# Sheet1.net
KiCad netlist of a schematic drawn in Altium Designer
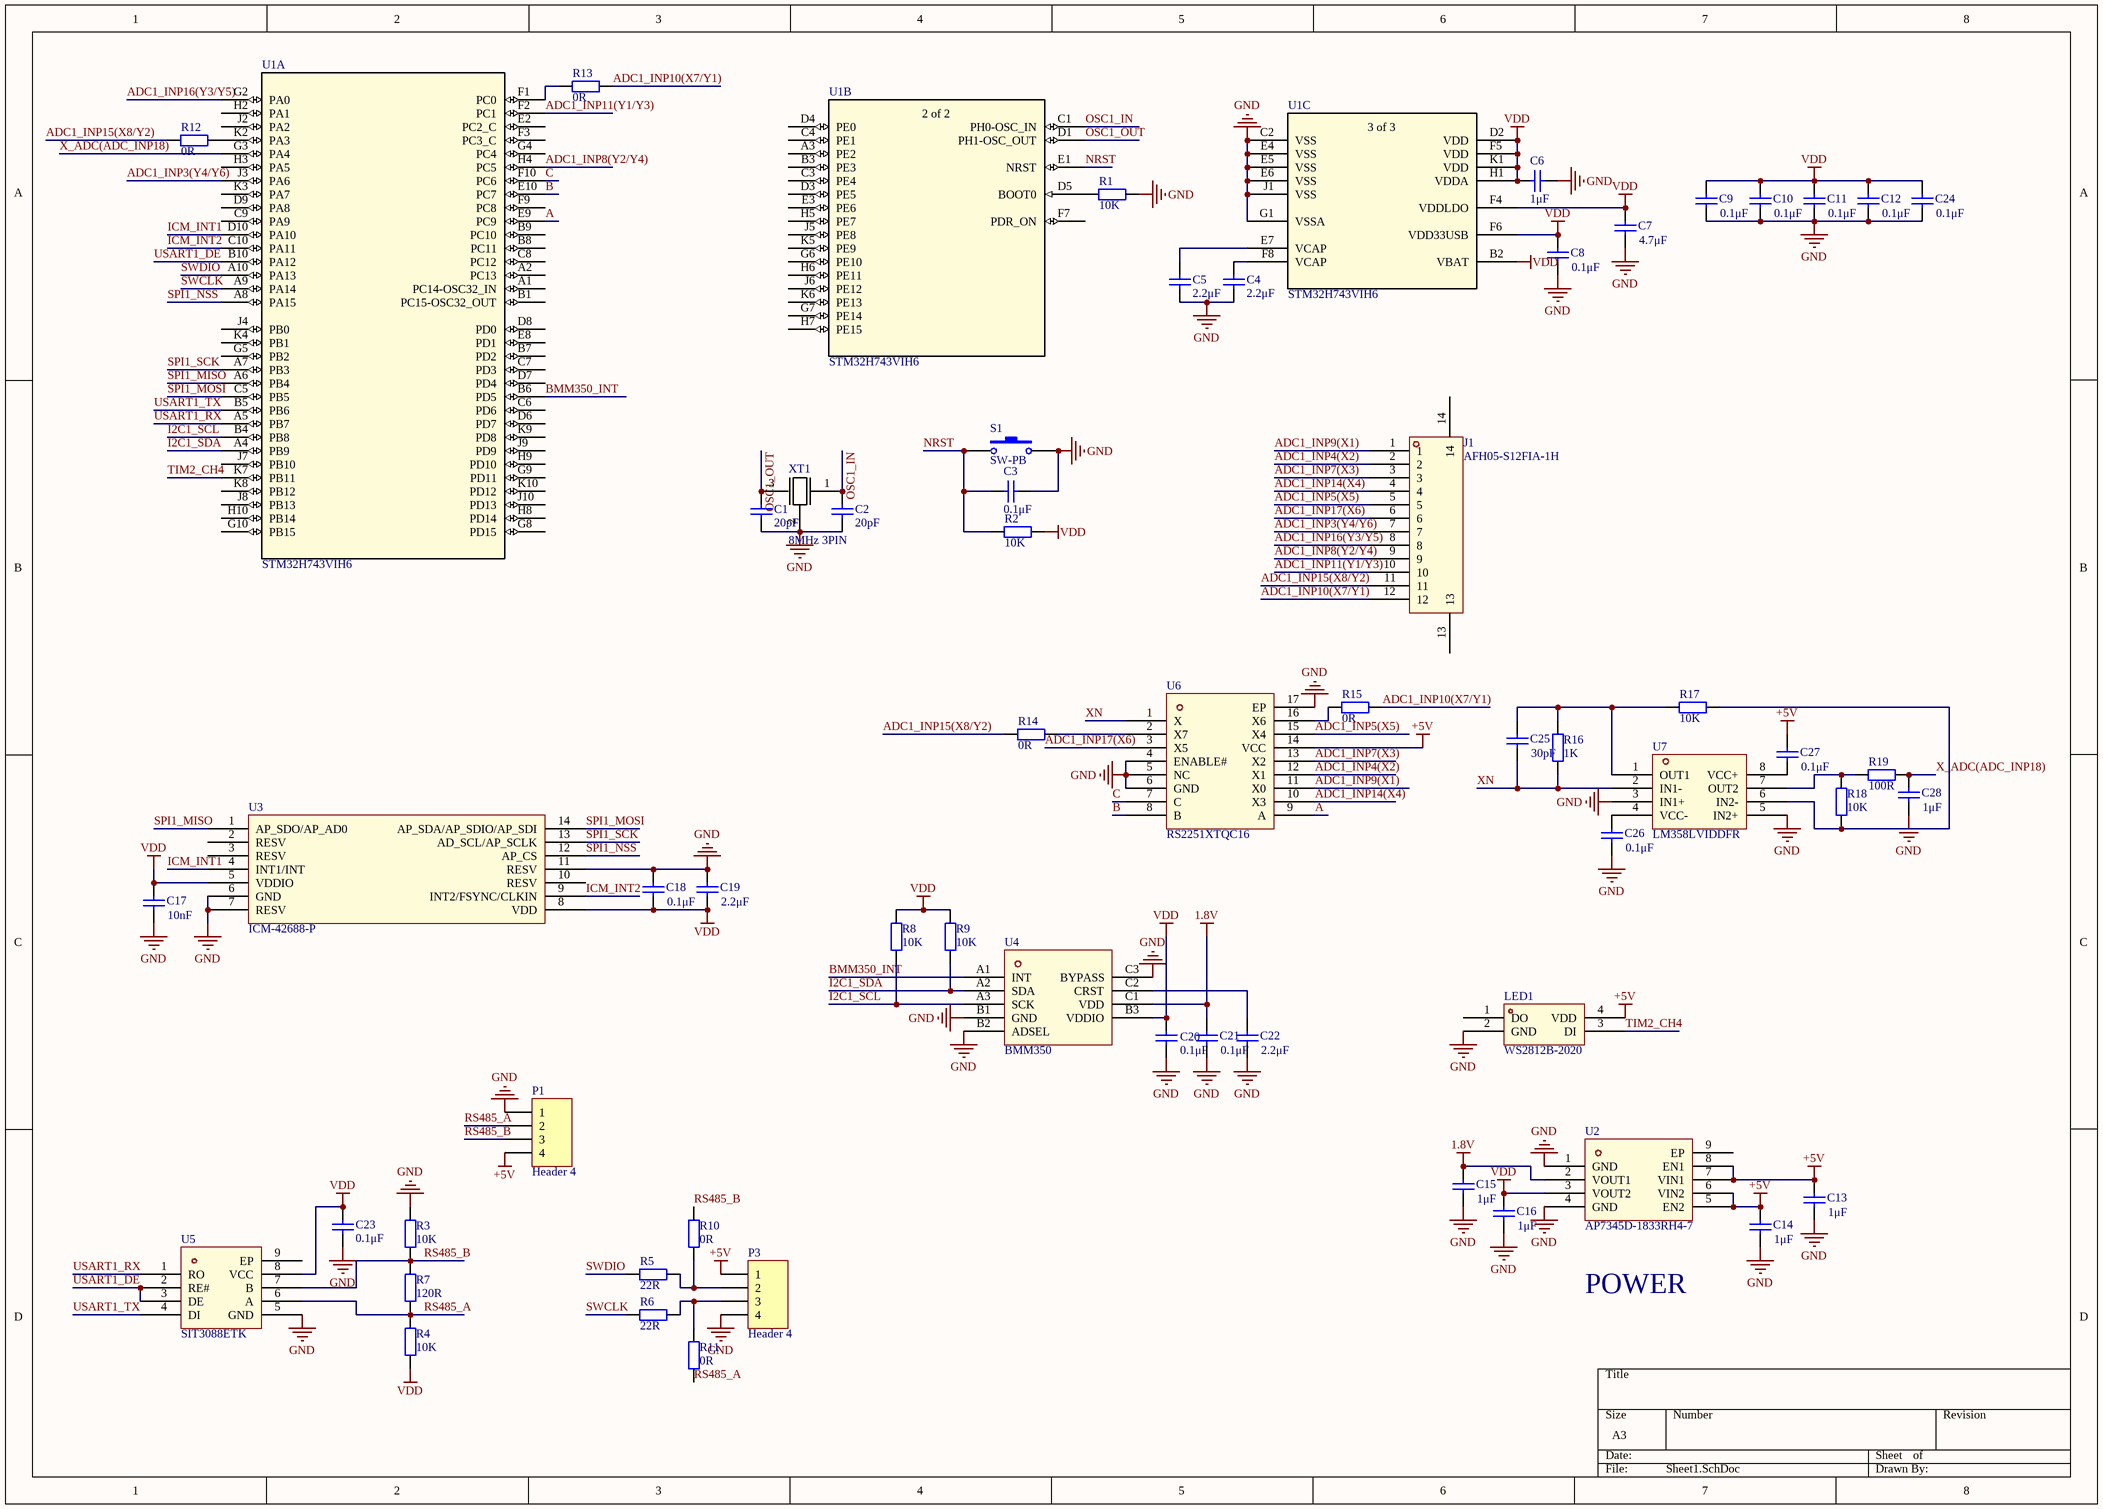
[diagram p0: Sheet1.SchDoc]

(export (version "E")
  (design (tool "Eeschema 10.0.6"))
  (components
    (comp (ref "C1")
      (value "20pF")
      (footprint "C0402")
      (description "Capacitor (Semiconductor SIM Model)")
      (fields (field (name "PUBLISHER") "Altium Limited"))
      (libsource (lib "Miscellaneous Devices") (part "Cap Semi"))
    )
    (comp (ref "C2")
      (value "20pF")
      (footprint "C0402")
      (description "Capacitor (Semiconductor SIM Model)")
      (fields (field (name "PUBLISHER") "Altium Limited"))
      (libsource (lib "Miscellaneous Devices") (part "Cap Semi"))
    )
    (comp (ref "C3")
      (value "0.1μF")
      (footprint "C0402")
      (description "Capacitor (Semiconductor SIM Model)")
      (fields (field (name "PUBLISHER") "Altium Limited"))
      (libsource (lib "Miscellaneous Devices") (part "Cap Semi"))
    )
    (comp (ref "C4")
      (value "2.2μF")
      (footprint "C0402")
      (description "Capacitor (Semiconductor SIM Model)")
      (fields (field (name "PUBLISHER") "Altium Limited"))
      (libsource (lib "Miscellaneous Devices") (part "Cap Semi"))
    )
    (comp (ref "C5")
      (value "2.2μF")
      (footprint "C0402")
      (description "Capacitor (Semiconductor SIM Model)")
      (fields (field (name "PUBLISHER") "Altium Limited"))
      (libsource (lib "Miscellaneous Devices") (part "Cap Semi"))
    )
    (comp (ref "C6")
      (value "1μF")
      (footprint "C0402")
      (description "Capacitor (Semiconductor SIM Model)")
      (fields (field (name "PUBLISHER") "Altium Limited"))
      (libsource (lib "Miscellaneous Devices") (part "Cap Semi"))
    )
    (comp (ref "C7")
      (value "4.7μF")
      (footprint "C0402")
      (description "Capacitor (Semiconductor SIM Model)")
      (fields (field (name "PUBLISHER") "Altium Limited"))
      (libsource (lib "Miscellaneous Devices") (part "Cap Semi"))
    )
    (comp (ref "C8")
      (value "0.1μF")
      (footprint "C0402")
      (description "Capacitor (Semiconductor SIM Model)")
      (fields (field (name "PUBLISHER") "Altium Limited"))
      (libsource (lib "Miscellaneous Devices") (part "Cap Semi"))
    )
    (comp (ref "C9")
      (value "0.1μF")
      (footprint "C0402")
      (description "Capacitor (Semiconductor SIM Model)")
      (fields (field (name "PUBLISHER") "Altium Limited"))
      (libsource (lib "Miscellaneous Devices") (part "Cap Semi"))
    )
    (comp (ref "C10")
      (value "0.1μF")
      (footprint "C0402")
      (description "Capacitor (Semiconductor SIM Model)")
      (fields (field (name "PUBLISHER") "Altium Limited"))
      (libsource (lib "Miscellaneous Devices") (part "Cap Semi"))
    )
    (comp (ref "C11")
      (value "0.1μF")
      (footprint "C0402")
      (description "Capacitor (Semiconductor SIM Model)")
      (fields (field (name "PUBLISHER") "Altium Limited"))
      (libsource (lib "Miscellaneous Devices") (part "Cap Semi"))
    )
    (comp (ref "C12")
      (value "0.1μF")
      (footprint "C0402")
      (description "Capacitor (Semiconductor SIM Model)")
      (fields (field (name "PUBLISHER") "Altium Limited"))
      (libsource (lib "Miscellaneous Devices") (part "Cap Semi"))
    )
    (comp (ref "C13")
      (value "1μF")
      (footprint "C0402")
      (description "Capacitor (Semiconductor SIM Model)")
      (fields (field (name "PUBLISHER") "Altium Limited"))
      (libsource (lib "Miscellaneous Devices") (part "Cap Semi"))
    )
    (comp (ref "C14")
      (value "1μF")
      (footprint "C0402")
      (description "Capacitor (Semiconductor SIM Model)")
      (fields (field (name "PUBLISHER") "Altium Limited"))
      (libsource (lib "Miscellaneous Devices") (part "Cap Semi"))
    )
    (comp (ref "C15")
      (value "1μF")
      (footprint "C0402")
      (description "Capacitor (Semiconductor SIM Model)")
      (fields (field (name "PUBLISHER") "Altium Limited"))
      (libsource (lib "Miscellaneous Devices") (part "Cap Semi"))
    )
    (comp (ref "C16")
      (value "1μF")
      (footprint "C0402")
      (description "Capacitor (Semiconductor SIM Model)")
      (fields (field (name "PUBLISHER") "Altium Limited"))
      (libsource (lib "Miscellaneous Devices") (part "Cap Semi"))
    )
    (comp (ref "C17")
      (value "10nF")
      (footprint "C0402")
      (description "Capacitor (Semiconductor SIM Model)")
      (fields (field (name "PUBLISHER") "Altium Limited"))
      (libsource (lib "Miscellaneous Devices") (part "Cap Semi"))
    )
    (comp (ref "C18")
      (value "0.1μF")
      (footprint "C0402")
      (description "Capacitor (Semiconductor SIM Model)")
      (fields (field (name "PUBLISHER") "Altium Limited"))
      (libsource (lib "Miscellaneous Devices") (part "Cap Semi"))
    )
    (comp (ref "C19")
      (value "2.2μF")
      (footprint "C0402")
      (description "Capacitor (Semiconductor SIM Model)")
      (fields (field (name "PUBLISHER") "Altium Limited"))
      (libsource (lib "Miscellaneous Devices") (part "Cap Semi"))
    )
    (comp (ref "C20")
      (value "0.1μF")
      (footprint "C0402")
      (description "Capacitor (Semiconductor SIM Model)")
      (fields (field (name "PUBLISHER") "Altium Limited"))
      (libsource (lib "Miscellaneous Devices") (part "Cap Semi"))
    )
    (comp (ref "C21")
      (value "0.1μF")
      (footprint "C0402")
      (description "Capacitor (Semiconductor SIM Model)")
      (fields (field (name "PUBLISHER") "Altium Limited"))
      (libsource (lib "Miscellaneous Devices") (part "Cap Semi"))
    )
    (comp (ref "C22")
      (value "2.2μF")
      (footprint "C0402")
      (description "Capacitor (Semiconductor SIM Model)")
      (fields (field (name "PUBLISHER") "Altium Limited"))
      (libsource (lib "Miscellaneous Devices") (part "Cap Semi"))
    )
    (comp (ref "C23")
      (value "0.1μF")
      (footprint "C0402")
      (description "Capacitor (Semiconductor SIM Model)")
      (fields (field (name "PUBLISHER") "Altium Limited"))
      (libsource (lib "Miscellaneous Devices") (part "Cap Semi"))
    )
    (comp (ref "C24")
      (value "0.1μF")
      (footprint "C0402")
      (description "Capacitor (Semiconductor SIM Model)")
      (fields (field (name "PUBLISHER") "Altium Limited"))
      (libsource (lib "Miscellaneous Devices") (part "Cap Semi"))
    )
    (comp (ref "C25")
      (value "30pF")
      (footprint "C0402")
      (description "Capacitor (Semiconductor SIM Model)")
      (fields (field (name "PUBLISHER") "Altium Limited"))
      (libsource (lib "Miscellaneous Devices") (part "Cap Semi"))
    )
    (comp (ref "C26")
      (value "0.1μF")
      (footprint "C0402")
      (description "Capacitor (Semiconductor SIM Model)")
      (fields (field (name "PUBLISHER") "Altium Limited"))
      (libsource (lib "Miscellaneous Devices") (part "Cap Semi"))
    )
    (comp (ref "C27")
      (value "0.1μF")
      (footprint "C0402")
      (description "Capacitor (Semiconductor SIM Model)")
      (fields (field (name "PUBLISHER") "Altium Limited"))
      (libsource (lib "Miscellaneous Devices") (part "Cap Semi"))
    )
    (comp (ref "C28")
      (value "1μF")
      (footprint "C0402")
      (description "Capacitor (Semiconductor SIM Model)")
      (fields (field (name "PUBLISHER") "Altium Limited"))
      (libsource (lib "Miscellaneous Devices") (part "Cap Semi"))
    )
    (comp (ref "J1")
      (value "AFH05-S12FIA-1H")
      (footprint "FPC-SMD_12P-P0.50_GT-F0501SR10-12S1101")
      (libsource (lib "Connectors") (part "AFH05-S12FIA-1H"))
    )
    (comp (ref "LED1")
      (value "WS2812B-2020")
      (footprint "LED-SMD_4P-L2.0-W2.0-TL_WS2812B-2020")
      (libsource (lib "Basic") (part "WS2812B-2020"))
    )
    (comp (ref "P1")
      (value "Header 4")
      (footprint "CONN-SMD_XDWF-0910-04P")
      (description "XDWF-0910-04P")
      (fields (field (name "PUBLISHER") "Altium Limited"))
      (libsource (lib "Miscellaneous Connectors") (part "Header 4"))
    )
    (comp (ref "P3")
      (value "Header 4")
      (footprint "CONN-SMD_XDWF-0910-04P")
      (description "XDWF-0910-04P")
      (fields (field (name "PUBLISHER") "Altium Limited"))
      (libsource (lib "Miscellaneous Connectors") (part "Header 4"))
    )
    (comp (ref "R1")
      (value "10K")
      (footprint "R0402")
      (description "Resistor")
      (fields (field (name "PUBLISHER") "Altium Limited"))
      (libsource (lib "") (part "Res2_3"))
    )
    (comp (ref "R2")
      (value "10K")
      (footprint "R0402")
      (description "Resistor")
      (fields (field (name "PUBLISHER") "Altium Limited"))
      (libsource (lib "Miscellaneous Devices") (part "Res2"))
    )
    (comp (ref "R3")
      (value "10K")
      (footprint "R0402")
      (description "Resistor")
      (fields (field (name "PUBLISHER") "Altium Limited"))
      (libsource (lib "") (part "Res2_2"))
    )
    (comp (ref "R4")
      (value "10K")
      (footprint "R0402")
      (description "Resistor")
      (fields (field (name "PUBLISHER") "Altium Limited"))
      (libsource (lib "") (part "Res2_2"))
    )
    (comp (ref "R5")
      (value "22R")
      (footprint "R0402")
      (description "Resistor")
      (fields (field (name "PUBLISHER") "Altium Limited"))
      (libsource (lib "Miscellaneous Devices") (part "Res2"))
    )
    (comp (ref "R6")
      (value "22R")
      (footprint "R0402")
      (description "Resistor")
      (fields (field (name "PUBLISHER") "Altium Limited"))
      (libsource (lib "Miscellaneous Devices") (part "Res2"))
    )
    (comp (ref "R7")
      (value "120R")
      (footprint "R0402")
      (description "Resistor")
      (fields (field (name "PUBLISHER") "Altium Limited"))
      (libsource (lib "") (part "Res2_1"))
    )
    (comp (ref "R8")
      (value "10K")
      (footprint "R0402")
      (description "Resistor")
      (fields (field (name "PUBLISHER") "Altium Limited"))
      (libsource (lib "") (part "Res2_2"))
    )
    (comp (ref "R9")
      (value "10K")
      (footprint "R0402")
      (description "Resistor")
      (fields (field (name "PUBLISHER") "Altium Limited"))
      (libsource (lib "") (part "Res2_2"))
    )
    (comp (ref "R10")
      (value "0R")
      (footprint "R0402")
      (description "Resistor")
      (fields (field (name "PUBLISHER") "Altium Limited"))
      (libsource (lib "") (part "Res2_1"))
    )
    (comp (ref "R11")
      (value "0R")
      (footprint "R0402")
      (description "Resistor")
      (fields (field (name "PUBLISHER") "Altium Limited"))
      (libsource (lib "") (part "Res2_1"))
    )
    (comp (ref "R12")
      (value "0R")
      (footprint "R0402")
      (description "Resistor\r\n6x6 Y2")
      (fields (field (name "PUBLISHER") "Altium Limited"))
      (libsource (lib "") (part "Res2_3"))
    )
    (comp (ref "R13")
      (value "0R")
      (footprint "R0402")
      (description "Resistor\r\n6x6 Y1")
      (fields (field (name "PUBLISHER") "Altium Limited"))
      (libsource (lib "") (part "Res2_3"))
    )
    (comp (ref "R14")
      (value "0R")
      (footprint "R0402")
      (description "Resistor\r\n4x8 X8")
      (fields (field (name "PUBLISHER") "Altium Limited"))
      (libsource (lib "") (part "Res2_3"))
    )
    (comp (ref "R15")
      (value "0R")
      (footprint "R0402")
      (description "Resistor\r\n4x8 X7")
      (fields (field (name "PUBLISHER") "Altium Limited"))
      (libsource (lib "") (part "Res2_3"))
    )
    (comp (ref "R16")
      (value "1K")
      (footprint "R0402")
      (description "Resistor")
      (fields (field (name "PUBLISHER") "Altium Limited"))
      (libsource (lib "") (part "Res2_1"))
    )
    (comp (ref "R17")
      (value "10K")
      (footprint "R0402")
      (description "Resistor")
      (fields (field (name "PUBLISHER") "Altium Limited"))
      (libsource (lib "Miscellaneous Devices") (part "Res2"))
    )
    (comp (ref "R18")
      (value "10K")
      (footprint "R0402")
      (description "Resistor")
      (fields (field (name "PUBLISHER") "Altium Limited"))
      (libsource (lib "") (part "Res2_1"))
    )
    (comp (ref "R19")
      (value "100R")
      (footprint "R0402")
      (description "Resistor")
      (fields (field (name "PUBLISHER") "Altium Limited"))
      (libsource (lib "Miscellaneous Devices") (part "Res2"))
    )
    (comp (ref "S1")
      (value "SW-PB")
      (footprint "SW-SMD_L3.9-W3.0-P4.45")
      (description "TS-1088R-02026")
      (fields (field (name "PUBLISHER") "Altium Limited"))
      (libsource (lib "Miscellaneous Devices") (part "SW-PB"))
    )
    (comp (ref "U1")
      (value "STM32H743VIH6")
      (footprint "TFBGA100")
      (description "No Description Available")
      (libsource (lib "STM32H743VIH6") (part "STM32H743VIH6"))
    )
    (comp (ref "U2")
      (value "AP7345D-1833RH4-7")
      (footprint "XDFN-8_L1.6-W1.2-P0.40-BL-EP")
      (libsource (lib "Power") (part "AP7345D-1833RH4-7"))
    )
    (comp (ref "U3")
      (value "ICM-42688-P")
      (footprint "LGA-14_L3.0-W2.5-P0.50-TL")
      (libsource (lib "Sensors") (part "ICM-42688-P"))
    )
    (comp (ref "U4")
      (value "BMM350")
      (footprint "WLCSP-9_L1.3-W1.3-R3-C3-P0.40-TL")
      (libsource (lib "Sensors") (part "BMM350"))
    )
    (comp (ref "U5")
      (value "SIT3088ETK")
      (footprint "DFN-8_L3.0-W3.0-P0.65-BL-EP")
      (libsource (lib "Basic") (part "SIT3088ETK"))
    )
    (comp (ref "U6")
      (value "RS2251XTQC16")
      (footprint "QFN-16_L3.0-W3.0-P0.50-BL-EP1.7")
      (libsource (lib "Basic") (part "RS2251XTQC16"))
    )
    (comp (ref "U7")
      (value "LM358LVIDDFR")
      (footprint "SOT-23-8_L2.9-W1.6-P0.65-LS2.8-BR")
      (libsource (lib "Basic") (part "LM358LVIDDFR"))
    )
    (comp (ref "XT1")
      (value "8MHz 3PIN")
      (footprint "8MHz 0.07% OSC-SMD_3P-L3.2-W1.3-P1.20-L")
      (description "CSTNE8M00GH5C000R0")
      (libsource (lib "Schlibs") (part "8MHz 0.07% 3PIN_1"))
    )
  )
  (nets
    (net (code "1") (name "+5V") (class "Default")
      (node (ref "C13") (pin "2") (pinfunction "2_2") (pintype "passive"))
      (node (ref "C14") (pin "2") (pinfunction "2_2") (pintype "passive"))
      (node (ref "C27") (pin "2") (pinfunction "2_2") (pintype "passive"))
      (node (ref "LED1") (pin "4") (pinfunction "VDD_4") (pintype "passive"))
      (node (ref "P1") (pin "4") (pinfunction "4_4") (pintype "passive"))
      (node (ref "P3") (pin "1") (pinfunction "1_1") (pintype "passive"))
      (node (ref "U2") (pin "5") (pinfunction "EN2_5") (pintype "passive"))
      (node (ref "U2") (pin "6") (pinfunction "VIN2_6") (pintype "passive"))
      (node (ref "U2") (pin "7") (pinfunction "VIN1_7") (pintype "passive"))
      (node (ref "U2") (pin "8") (pinfunction "EN1_8") (pintype "passive"))
      (node (ref "U6") (pin "14") (pinfunction "VCC_14") (pintype "passive"))
    )
    (net (code "2") (name "/A") (class "Default")
      (node (ref "U1") (pin "E9") (pinfunction "PC9_E9") (pintype "bidirectional"))
      (node (ref "U6") (pin "9") (pinfunction "A_9") (pintype "passive"))
    )
    (net (code "3") (name "/ADC1_INP3(Y4{slash}Y6)") (class "Default")
      (node (ref "J1") (pin "7") (pinfunction "7_7") (pintype "passive"))
      (node (ref "U1") (pin "J3") (pinfunction "PA6_J3") (pintype "bidirectional"))
    )
    (net (code "4") (name "/ADC1_INP4(X2)") (class "Default")
      (node (ref "J1") (pin "2") (pinfunction "2_2") (pintype "passive"))
      (node (ref "U6") (pin "12") (pinfunction "X1_12") (pintype "passive"))
    )
    (net (code "5") (name "/ADC1_INP5(X5)") (class "Default")
      (node (ref "J1") (pin "5") (pinfunction "5_5") (pintype "passive"))
      (node (ref "U6") (pin "15") (pinfunction "X4_15") (pintype "passive"))
    )
    (net (code "6") (name "/ADC1_INP7(X3)") (class "Default")
      (node (ref "J1") (pin "3") (pinfunction "3_3") (pintype "passive"))
      (node (ref "U6") (pin "13") (pinfunction "X2_13") (pintype "passive"))
    )
    (net (code "7") (name "/ADC1_INP8(Y2{slash}Y4)") (class "Default")
      (node (ref "J1") (pin "9") (pinfunction "9_9") (pintype "passive"))
      (node (ref "U1") (pin "H4") (pinfunction "PC5_H4") (pintype "bidirectional"))
    )
    (net (code "8") (name "/ADC1_INP9(X1)") (class "Default")
      (node (ref "J1") (pin "1") (pinfunction "1_1") (pintype "passive"))
      (node (ref "U6") (pin "11") (pinfunction "X0_11") (pintype "passive"))
    )
    (net (code "9") (name "/ADC1_INP10(X7{slash}Y1)") (class "Default")
      (node (ref "J1") (pin "12") (pinfunction "12_12") (pintype "passive"))
      (node (ref "R13") (pin "1") (pinfunction "1_1") (pintype "passive"))
      (node (ref "R15") (pin "1") (pinfunction "1_1") (pintype "passive"))
    )
    (net (code "10") (name "/ADC1_INP11(Y1{slash}Y3)") (class "Default")
      (node (ref "J1") (pin "10") (pinfunction "10_10") (pintype "passive"))
      (node (ref "U1") (pin "F2") (pinfunction "PC1_F2") (pintype "bidirectional"))
    )
    (net (code "11") (name "/ADC1_INP14(X4)") (class "Default")
      (node (ref "J1") (pin "4") (pinfunction "4_4") (pintype "passive"))
      (node (ref "U6") (pin "10") (pinfunction "X3_10") (pintype "passive"))
    )
    (net (code "12") (name "/ADC1_INP15(X8{slash}Y2)") (class "Default")
      (node (ref "J1") (pin "11") (pinfunction "11_11") (pintype "passive"))
      (node (ref "R12") (pin "2") (pinfunction "2_2") (pintype "passive"))
      (node (ref "R14") (pin "2") (pinfunction "2_2") (pintype "passive"))
    )
    (net (code "13") (name "/ADC1_INP16(Y3{slash}Y5)") (class "Default")
      (node (ref "J1") (pin "8") (pinfunction "8_8") (pintype "passive"))
      (node (ref "U1") (pin "G2") (pinfunction "PA0_G2") (pintype "bidirectional"))
    )
    (net (code "14") (name "/ADC1_INP17(X6)") (class "Default")
      (node (ref "J1") (pin "6") (pinfunction "6_6") (pintype "passive"))
      (node (ref "U6") (pin "3") (pinfunction "X5_3") (pintype "passive"))
    )
    (net (code "15") (name "/B") (class "Default")
      (node (ref "U1") (pin "E10") (pinfunction "PC7_E10") (pintype "bidirectional"))
      (node (ref "U6") (pin "8") (pinfunction "B_8") (pintype "passive"))
    )
    (net (code "16") (name "/BMM350_INT") (class "Default")
      (node (ref "U1") (pin "B6") (pinfunction "PD5_B6") (pintype "bidirectional"))
      (node (ref "U4") (pin "A1") (pinfunction "INT_A1") (pintype "passive"))
    )
    (net (code "17") (name "/C") (class "Default")
      (node (ref "U1") (pin "F10") (pinfunction "PC6_F10") (pintype "bidirectional"))
      (node (ref "U6") (pin "7") (pinfunction "C_7") (pintype "passive"))
    )
    (net (code "18") (name "/I2C1_SCL") (class "Default")
      (node (ref "R8") (pin "2") (pinfunction "2_2") (pintype "passive"))
      (node (ref "U1") (pin "B4") (pinfunction "PB8_B4") (pintype "bidirectional"))
      (node (ref "U4") (pin "A3") (pinfunction "SCK_A3") (pintype "passive"))
    )
    (net (code "19") (name "/I2C1_SDA") (class "Default")
      (node (ref "R9") (pin "2") (pinfunction "2_2") (pintype "passive"))
      (node (ref "U1") (pin "A4") (pinfunction "PB9_A4") (pintype "bidirectional"))
      (node (ref "U4") (pin "A2") (pinfunction "SDA_A2") (pintype "passive"))
    )
    (net (code "20") (name "/ICM_INT1") (class "Default")
      (node (ref "U1") (pin "D10") (pinfunction "PA10_D10") (pintype "bidirectional"))
      (node (ref "U3") (pin "4") (pinfunction "INT1/INT_4") (pintype "passive"))
    )
    (net (code "21") (name "/ICM_INT2") (class "Default")
      (node (ref "U1") (pin "C10") (pinfunction "PA11_C10") (pintype "bidirectional"))
      (node (ref "U3") (pin "9") (pinfunction "INT2/FSYNC/CLKIN_9") (pintype "passive"))
    )
    (net (code "22") (name "/NRST") (class "Default")
      (node (ref "C3") (pin "1") (pinfunction "1_1") (pintype "passive"))
      (node (ref "R2") (pin "1") (pinfunction "1_1") (pintype "passive"))
      (node (ref "S1") (pin "1") (pinfunction "1_1") (pintype "passive"))
      (node (ref "U1") (pin "E1") (pinfunction "NRST_E1") (pintype "bidirectional"))
    )
    (net (code "23") (name "/OSC1_IN") (class "Default")
      (node (ref "C2") (pin "2") (pinfunction "2_2") (pintype "passive"))
      (node (ref "U1") (pin "C1") (pinfunction "PH0-OSC_IN_C1") (pintype "bidirectional"))
      (node (ref "XT1") (pin "1") (pinfunction "OUTPUT_1") (pintype "passive"))
    )
    (net (code "24") (name "/OSC1_OUT") (class "Default")
      (node (ref "C1") (pin "2") (pinfunction "2_2") (pintype "passive"))
      (node (ref "U1") (pin "D1") (pinfunction "PH1-OSC_OUT_D1") (pintype "bidirectional"))
      (node (ref "XT1") (pin "3") (pinfunction "INPUT_3") (pintype "passive"))
    )
    (net (code "25") (name "/RS485_A") (class "Default")
      (node (ref "P1") (pin "2") (pinfunction "2_2") (pintype "passive"))
      (node (ref "R11") (pin "1") (pinfunction "1_1") (pintype "passive"))
      (node (ref "R4") (pin "1") (pinfunction "1_1") (pintype "passive"))
      (node (ref "R7") (pin "1") (pinfunction "1_1") (pintype "passive"))
      (node (ref "U5") (pin "6") (pinfunction "A_6") (pintype "passive"))
    )
    (net (code "26") (name "/RS485_B") (class "Default")
      (node (ref "P1") (pin "3") (pinfunction "3_3") (pintype "passive"))
      (node (ref "R10") (pin "2") (pinfunction "2_2") (pintype "passive"))
      (node (ref "R3") (pin "2") (pinfunction "2_2") (pintype "passive"))
      (node (ref "R7") (pin "2") (pinfunction "2_2") (pintype "passive"))
      (node (ref "U5") (pin "7") (pinfunction "B_7") (pintype "passive"))
    )
    (net (code "27") (name "/SPI1_MISO") (class "Default")
      (node (ref "U1") (pin "A6") (pinfunction "PB4_A6") (pintype "bidirectional"))
      (node (ref "U3") (pin "1") (pinfunction "AP_SDO/AP_AD0_1") (pintype "passive"))
    )
    (net (code "28") (name "/SPI1_MOSI") (class "Default")
      (node (ref "U1") (pin "C5") (pinfunction "PB5_C5") (pintype "bidirectional"))
      (node (ref "U3") (pin "14") (pinfunction "AP_SDA/AP_SDIO/AP_SDI_14") (pintype "passive"))
    )
    (net (code "29") (name "/SPI1_NSS") (class "Default")
      (node (ref "U1") (pin "A8") (pinfunction "PA15_A8") (pintype "bidirectional"))
      (node (ref "U3") (pin "12") (pinfunction "AP_CS_12") (pintype "passive"))
    )
    (net (code "30") (name "/SPI1_SCK") (class "Default")
      (node (ref "U1") (pin "A7") (pinfunction "PB3_A7") (pintype "bidirectional"))
      (node (ref "U3") (pin "13") (pinfunction "AD_SCL/AP_SCLK_13") (pintype "passive"))
    )
    (net (code "31") (name "/SWCLK") (class "Default")
      (node (ref "R6") (pin "1") (pinfunction "1_1") (pintype "passive"))
      (node (ref "U1") (pin "A9") (pinfunction "PA14_A9") (pintype "bidirectional"))
    )
    (net (code "32") (name "/SWDIO") (class "Default")
      (node (ref "R5") (pin "1") (pinfunction "1_1") (pintype "passive"))
      (node (ref "U1") (pin "A10") (pinfunction "PA13_A10") (pintype "bidirectional"))
    )
    (net (code "33") (name "/TIM2_CH4") (class "Default")
      (node (ref "LED1") (pin "3") (pinfunction "DI_3") (pintype "passive"))
      (node (ref "U1") (pin "K7") (pinfunction "PB11_K7") (pintype "bidirectional"))
    )
    (net (code "34") (name "/USART1_DE") (class "Default")
      (node (ref "U1") (pin "B10") (pinfunction "PA12_B10") (pintype "bidirectional"))
      (node (ref "U5") (pin "2") (pinfunction "RE#_2") (pintype "passive"))
      (node (ref "U5") (pin "3") (pinfunction "DE_3") (pintype "passive"))
    )
    (net (code "35") (name "/USART1_RX") (class "Default")
      (node (ref "U1") (pin "A5") (pinfunction "PB7_A5") (pintype "bidirectional"))
      (node (ref "U5") (pin "1") (pinfunction "RO_1") (pintype "passive"))
    )
    (net (code "36") (name "/USART1_TX") (class "Default")
      (node (ref "U1") (pin "B5") (pinfunction "PB6_B5") (pintype "bidirectional"))
      (node (ref "U5") (pin "4") (pinfunction "DI_4") (pintype "passive"))
    )
    (net (code "37") (name "/XN") (class "Default")
      (node (ref "C25") (pin "1") (pinfunction "1_1") (pintype "passive"))
      (node (ref "R16") (pin "1") (pinfunction "1_1") (pintype "passive"))
      (node (ref "U6") (pin "1") (pinfunction "X_1") (pintype "passive"))
      (node (ref "U7") (pin "2") (pinfunction "IN1-_2") (pintype "passive"))
    )
    (net (code "38") (name "/X_ADC(ADC_INP18)") (class "Default")
      (node (ref "C28") (pin "2") (pinfunction "2_2") (pintype "passive"))
      (node (ref "R19") (pin "2") (pinfunction "2_2") (pintype "passive"))
      (node (ref "U1") (pin "G3") (pinfunction "PA4_G3") (pintype "bidirectional"))
    )
    (net (code "39") (name "1.8V") (class "Default")
      (node (ref "C15") (pin "2") (pinfunction "2_2") (pintype "passive"))
      (node (ref "C21") (pin "2") (pinfunction "2_2") (pintype "passive"))
      (node (ref "U2") (pin "2") (pinfunction "VOUT1_2") (pintype "passive"))
      (node (ref "U4") (pin "C1") (pinfunction "VDD_C1") (pintype "passive"))
    )
    (net (code "40") (name "GND") (class "Default")
      (node (ref "C1") (pin "1") (pinfunction "1_1") (pintype "passive"))
      (node (ref "C10") (pin "1") (pinfunction "1_1") (pintype "passive"))
      (node (ref "C11") (pin "1") (pinfunction "1_1") (pintype "passive"))
      (node (ref "C12") (pin "1") (pinfunction "1_1") (pintype "passive"))
      (node (ref "C13") (pin "1") (pinfunction "1_1") (pintype "passive"))
      (node (ref "C14") (pin "1") (pinfunction "1_1") (pintype "passive"))
      (node (ref "C15") (pin "1") (pinfunction "1_1") (pintype "passive"))
      (node (ref "C16") (pin "1") (pinfunction "1_1") (pintype "passive"))
      (node (ref "C17") (pin "1") (pinfunction "1_1") (pintype "passive"))
      (node (ref "C18") (pin "2") (pinfunction "2_2") (pintype "passive"))
      (node (ref "C19") (pin "2") (pinfunction "2_2") (pintype "passive"))
      (node (ref "C2") (pin "1") (pinfunction "1_1") (pintype "passive"))
      (node (ref "C20") (pin "1") (pinfunction "1_1") (pintype "passive"))
      (node (ref "C21") (pin "1") (pinfunction "1_1") (pintype "passive"))
      (node (ref "C22") (pin "1") (pinfunction "1_1") (pintype "passive"))
      (node (ref "C23") (pin "1") (pinfunction "1_1") (pintype "passive"))
      (node (ref "C24") (pin "1") (pinfunction "1_1") (pintype "passive"))
      (node (ref "C26") (pin "1") (pinfunction "1_1") (pintype "passive"))
      (node (ref "C28") (pin "1") (pinfunction "1_1") (pintype "passive"))
      (node (ref "C3") (pin "2") (pinfunction "2_2") (pintype "passive"))
      (node (ref "C4") (pin "1") (pinfunction "1_1") (pintype "passive"))
      (node (ref "C5") (pin "1") (pinfunction "1_1") (pintype "passive"))
      (node (ref "C6") (pin "1") (pinfunction "1_1") (pintype "passive"))
      (node (ref "C7") (pin "1") (pinfunction "1_1") (pintype "passive"))
      (node (ref "C8") (pin "1") (pinfunction "1_1") (pintype "passive"))
      (node (ref "C9") (pin "1") (pinfunction "1_1") (pintype "passive"))
      (node (ref "LED1") (pin "2") (pinfunction "GND_2") (pintype "passive"))
      (node (ref "P1") (pin "1") (pinfunction "1_1") (pintype "passive"))
      (node (ref "P3") (pin "4") (pinfunction "4_4") (pintype "passive"))
      (node (ref "R1") (pin "1") (pinfunction "1_1") (pintype "passive"))
      (node (ref "R3") (pin "1") (pinfunction "1_1") (pintype "passive"))
      (node (ref "S1") (pin "2") (pinfunction "2_2") (pintype "passive"))
      (node (ref "U1") (pin "C2") (pinfunction "VSS_C2") (pintype "power_in"))
      (node (ref "U1") (pin "E4") (pinfunction "VSS_E4") (pintype "power_in"))
      (node (ref "U1") (pin "E5") (pinfunction "VSS_E5") (pintype "power_in"))
      (node (ref "U1") (pin "E6") (pinfunction "VSS_E6") (pintype "power_in"))
      (node (ref "U1") (pin "G1") (pinfunction "VSSA_G1") (pintype "power_in"))
      (node (ref "U1") (pin "J1") (pinfunction "VSS_J1") (pintype "power_in"))
      (node (ref "U2") (pin "1") (pinfunction "GND_1") (pintype "passive"))
      (node (ref "U2") (pin "4") (pinfunction "GND_4") (pintype "passive"))
      (node (ref "U3") (pin "11") (pinfunction "RESV_11") (pintype "passive"))
      (node (ref "U3") (pin "6") (pinfunction "GND_6") (pintype "passive"))
      (node (ref "U3") (pin "7") (pinfunction "RESV_7") (pintype "passive"))
      (node (ref "U4") (pin "B1") (pinfunction "GND_B1") (pintype "passive"))
      (node (ref "U4") (pin "B2") (pinfunction "ADSEL_B2") (pintype "passive"))
      (node (ref "U4") (pin "C3") (pinfunction "BYPASS_C3") (pintype "passive"))
      (node (ref "U5") (pin "5") (pinfunction "GND_5") (pintype "passive"))
      (node (ref "U6") (pin "17") (pinfunction "EP_17") (pintype "passive"))
      (node (ref "U6") (pin "4") (pinfunction "ENABLE#_4") (pintype "passive"))
      (node (ref "U6") (pin "5") (pinfunction "NC_5") (pintype "passive"))
      (node (ref "U6") (pin "6") (pinfunction "GND_6") (pintype "passive"))
      (node (ref "U7") (pin "3") (pinfunction "IN1+_3") (pintype "passive"))
      (node (ref "U7") (pin "5") (pinfunction "IN2+_5") (pintype "passive"))
      (node (ref "XT1") (pin "2") (pinfunction "GND_2") (pintype "passive"))
    )
    (net (code "41") (name "Net-(C4-Pad2)") (class "Default")
      (node (ref "C4") (pin "2") (pinfunction "2_2") (pintype "passive"))
      (node (ref "U1") (pin "F8") (pinfunction "VCAP_F8") (pintype "power_in"))
    )
    (net (code "42") (name "Net-(C5-Pad2)") (class "Default")
      (node (ref "C5") (pin "2") (pinfunction "2_2") (pintype "passive"))
      (node (ref "U1") (pin "E7") (pinfunction "VCAP_E7") (pintype "power_in"))
    )
    (net (code "43") (name "Net-(P3-Pad2)") (class "Default")
      (node (ref "P3") (pin "2") (pinfunction "2_2") (pintype "passive"))
      (node (ref "R10") (pin "1") (pinfunction "1_1") (pintype "passive"))
      (node (ref "R5") (pin "2") (pinfunction "2_2") (pintype "passive"))
    )
    (net (code "44") (name "Net-(P3-Pad3)") (class "Default")
      (node (ref "P3") (pin "3") (pinfunction "3_3") (pintype "passive"))
      (node (ref "R11") (pin "2") (pinfunction "2_2") (pintype "passive"))
      (node (ref "R6") (pin "2") (pinfunction "2_2") (pintype "passive"))
    )
    (net (code "45") (name "Net-(U1A-PA3)") (class "Default")
      (node (ref "R12") (pin "1") (pinfunction "1_1") (pintype "passive"))
      (node (ref "U1") (pin "K2") (pinfunction "PA3_K2") (pintype "bidirectional"))
    )
    (net (code "46") (name "Net-(U1A-PC0)") (class "Default")
      (node (ref "R13") (pin "2") (pinfunction "2_2") (pintype "passive"))
      (node (ref "U1") (pin "F1") (pinfunction "PC0_F1") (pintype "bidirectional"))
    )
    (net (code "47") (name "Net-(U1B-BOOT0)") (class "Default")
      (node (ref "R1") (pin "2") (pinfunction "2_2") (pintype "passive"))
      (node (ref "U1") (pin "D5") (pinfunction "BOOT0_D5") (pintype "input"))
    )
    (net (code "48") (name "Net-(U4-CRST)") (class "Default")
      (node (ref "C22") (pin "2") (pinfunction "2_2") (pintype "passive"))
      (node (ref "U4") (pin "C2") (pinfunction "CRST_C2") (pintype "passive"))
    )
    (net (code "49") (name "Net-(U6-X6)") (class "Default")
      (node (ref "R15") (pin "2") (pinfunction "2_2") (pintype "passive"))
      (node (ref "U6") (pin "16") (pinfunction "X6_16") (pintype "passive"))
    )
    (net (code "50") (name "Net-(U6-X7)") (class "Default")
      (node (ref "R14") (pin "1") (pinfunction "1_1") (pintype "passive"))
      (node (ref "U6") (pin "2") (pinfunction "X7_2") (pintype "passive"))
    )
    (net (code "51") (name "Net-(U7-IN2-)") (class "Default")
      (node (ref "R17") (pin "2") (pinfunction "2_2") (pintype "passive"))
      (node (ref "R18") (pin "1") (pinfunction "1_1") (pintype "passive"))
      (node (ref "U7") (pin "6") (pinfunction "IN2-_6") (pintype "passive"))
    )
    (net (code "52") (name "Net-(U7-OUT1)") (class "Default")
      (node (ref "C25") (pin "2") (pinfunction "2_2") (pintype "passive"))
      (node (ref "R16") (pin "2") (pinfunction "2_2") (pintype "passive"))
      (node (ref "R17") (pin "1") (pinfunction "1_1") (pintype "passive"))
      (node (ref "U7") (pin "1") (pinfunction "OUT1_1") (pintype "passive"))
    )
    (net (code "53") (name "Net-(U7-OUT2)") (class "Default")
      (node (ref "R18") (pin "2") (pinfunction "2_2") (pintype "passive"))
      (node (ref "R19") (pin "1") (pinfunction "1_1") (pintype "passive"))
      (node (ref "U7") (pin "7") (pinfunction "OUT2_7") (pintype "passive"))
    )
    (net (code "54") (name "Net-(U7-VCC+)") (class "Default")
      (node (ref "C27") (pin "1") (pinfunction "1_1") (pintype "passive"))
      (node (ref "U7") (pin "8") (pinfunction "VCC+_8") (pintype "passive"))
    )
    (net (code "55") (name "Net-(U7-VCC-)") (class "Default")
      (node (ref "C26") (pin "2") (pinfunction "2_2") (pintype "passive"))
      (node (ref "U7") (pin "4") (pinfunction "VCC-_4") (pintype "passive"))
    )
    (net (code "56") (name "VDD") (class "Default")
      (node (ref "C10") (pin "2") (pinfunction "2_2") (pintype "passive"))
      (node (ref "C11") (pin "2") (pinfunction "2_2") (pintype "passive"))
      (node (ref "C12") (pin "2") (pinfunction "2_2") (pintype "passive"))
      (node (ref "C16") (pin "2") (pinfunction "2_2") (pintype "passive"))
      (node (ref "C17") (pin "2") (pinfunction "2_2") (pintype "passive"))
      (node (ref "C18") (pin "1") (pinfunction "1_1") (pintype "passive"))
      (node (ref "C19") (pin "1") (pinfunction "1_1") (pintype "passive"))
      (node (ref "C20") (pin "2") (pinfunction "2_2") (pintype "passive"))
      (node (ref "C23") (pin "2") (pinfunction "2_2") (pintype "passive"))
      (node (ref "C24") (pin "2") (pinfunction "2_2") (pintype "passive"))
      (node (ref "C6") (pin "2") (pinfunction "2_2") (pintype "passive"))
      (node (ref "C7") (pin "2") (pinfunction "2_2") (pintype "passive"))
      (node (ref "C8") (pin "2") (pinfunction "2_2") (pintype "passive"))
      (node (ref "C9") (pin "2") (pinfunction "2_2") (pintype "passive"))
      (node (ref "R2") (pin "2") (pinfunction "2_2") (pintype "passive"))
      (node (ref "R4") (pin "2") (pinfunction "2_2") (pintype "passive"))
      (node (ref "R8") (pin "1") (pinfunction "1_1") (pintype "passive"))
      (node (ref "R9") (pin "1") (pinfunction "1_1") (pintype "passive"))
      (node (ref "U1") (pin "B2") (pinfunction "VBAT_B2") (pintype "power_in"))
      (node (ref "U1") (pin "D2") (pinfunction "VDD_D2") (pintype "power_in"))
      (node (ref "U1") (pin "F4") (pinfunction "VDDLDO_F4") (pintype "power_in"))
      (node (ref "U1") (pin "F5") (pinfunction "VDD_F5") (pintype "power_in"))
      (node (ref "U1") (pin "F6") (pinfunction "VDD33USB_F6") (pintype "power_in"))
      (node (ref "U1") (pin "H1") (pinfunction "VDDA_H1") (pintype "power_in"))
      (node (ref "U1") (pin "K1") (pinfunction "VDD_K1") (pintype "power_in"))
      (node (ref "U2") (pin "3") (pinfunction "VOUT2_3") (pintype "passive"))
      (node (ref "U3") (pin "5") (pinfunction "VDDIO_5") (pintype "passive"))
      (node (ref "U3") (pin "8") (pinfunction "VDD_8") (pintype "passive"))
      (node (ref "U4") (pin "B3") (pinfunction "VDDIO_B3") (pintype "passive"))
      (node (ref "U5") (pin "8") (pinfunction "VCC_8") (pintype "passive"))
    )
    (net (code "57") (name "unconnected-(J1-Pad13)") (class "Default")
      (node (ref "J1") (pin "13") (pinfunction "13_13") (pintype "passive"))
    )
    (net (code "58") (name "unconnected-(J1-Pad14)") (class "Default")
      (node (ref "J1") (pin "14") (pinfunction "14_14") (pintype "passive"))
    )
    (net (code "59") (name "unconnected-(LED1-DO-Pad1)") (class "Default")
      (node (ref "LED1") (pin "1") (pinfunction "DO_1") (pintype "passive"))
    )
    (net (code "60") (name "unconnected-(U1A-PA1-PadH2)") (class "Default")
      (node (ref "U1") (pin "H2") (pinfunction "PA1_H2") (pintype "bidirectional"))
    )
    (net (code "61") (name "unconnected-(U1A-PA2-PadJ2)") (class "Default")
      (node (ref "U1") (pin "J2") (pinfunction "PA2_J2") (pintype "bidirectional"))
    )
    (net (code "62") (name "unconnected-(U1A-PA5-PadH3)") (class "Default")
      (node (ref "U1") (pin "H3") (pinfunction "PA5_H3") (pintype "bidirectional"))
    )
    (net (code "63") (name "unconnected-(U1A-PA7-PadK3)") (class "Default")
      (node (ref "U1") (pin "K3") (pinfunction "PA7_K3") (pintype "bidirectional"))
    )
    (net (code "64") (name "unconnected-(U1A-PA8-PadD9)") (class "Default")
      (node (ref "U1") (pin "D9") (pinfunction "PA8_D9") (pintype "bidirectional"))
    )
    (net (code "65") (name "unconnected-(U1A-PA9-PadC9)") (class "Default")
      (node (ref "U1") (pin "C9") (pinfunction "PA9_C9") (pintype "bidirectional"))
    )
    (net (code "66") (name "unconnected-(U1A-PB0-PadJ4)") (class "Default")
      (node (ref "U1") (pin "J4") (pinfunction "PB0_J4") (pintype "bidirectional"))
    )
    (net (code "67") (name "unconnected-(U1A-PB1-PadK4)") (class "Default")
      (node (ref "U1") (pin "K4") (pinfunction "PB1_K4") (pintype "bidirectional"))
    )
    (net (code "68") (name "unconnected-(U1A-PB2-PadG5)") (class "Default")
      (node (ref "U1") (pin "G5") (pinfunction "PB2_G5") (pintype "bidirectional"))
    )
    (net (code "69") (name "unconnected-(U1A-PB10-PadJ7)") (class "Default")
      (node (ref "U1") (pin "J7") (pinfunction "PB10_J7") (pintype "bidirectional"))
    )
    (net (code "70") (name "unconnected-(U1A-PB12-PadK8)") (class "Default")
      (node (ref "U1") (pin "K8") (pinfunction "PB12_K8") (pintype "bidirectional"))
    )
    (net (code "71") (name "unconnected-(U1A-PB13-PadJ8)") (class "Default")
      (node (ref "U1") (pin "J8") (pinfunction "PB13_J8") (pintype "bidirectional"))
    )
    (net (code "72") (name "unconnected-(U1A-PB14-PadH10)") (class "Default")
      (node (ref "U1") (pin "H10") (pinfunction "PB14_H10") (pintype "bidirectional"))
    )
    (net (code "73") (name "unconnected-(U1A-PB15-PadG10)") (class "Default")
      (node (ref "U1") (pin "G10") (pinfunction "PB15_G10") (pintype "bidirectional"))
    )
    (net (code "74") (name "unconnected-(U1A-PC2_C-PadE2)") (class "Default")
      (node (ref "U1") (pin "E2") (pinfunction "PC2_C_E2") (pintype "bidirectional"))
    )
    (net (code "75") (name "unconnected-(U1A-PC3_C-PadF3)") (class "Default")
      (node (ref "U1") (pin "F3") (pinfunction "PC3_C_F3") (pintype "bidirectional"))
    )
    (net (code "76") (name "unconnected-(U1A-PC4-PadG4)") (class "Default")
      (node (ref "U1") (pin "G4") (pinfunction "PC4_G4") (pintype "bidirectional"))
    )
    (net (code "77") (name "unconnected-(U1A-PC8-PadF9)") (class "Default")
      (node (ref "U1") (pin "F9") (pinfunction "PC8_F9") (pintype "bidirectional"))
    )
    (net (code "78") (name "unconnected-(U1A-PC10-PadB9)") (class "Default")
      (node (ref "U1") (pin "B9") (pinfunction "PC10_B9") (pintype "bidirectional"))
    )
    (net (code "79") (name "unconnected-(U1A-PC11-PadB8)") (class "Default")
      (node (ref "U1") (pin "B8") (pinfunction "PC11_B8") (pintype "bidirectional"))
    )
    (net (code "80") (name "unconnected-(U1A-PC12-PadC8)") (class "Default")
      (node (ref "U1") (pin "C8") (pinfunction "PC12_C8") (pintype "bidirectional"))
    )
    (net (code "81") (name "unconnected-(U1A-PC13-PadA2)") (class "Default")
      (node (ref "U1") (pin "A2") (pinfunction "PC13_A2") (pintype "bidirectional"))
    )
    (net (code "82") (name "unconnected-(U1A-PC14-OSC32_IN-PadA1)") (class "Default")
      (node (ref "U1") (pin "A1") (pinfunction "PC14-OSC32_IN_A1") (pintype "bidirectional"))
    )
    (net (code "83") (name "unconnected-(U1A-PC15-OSC32_OUT-PadB1)") (class "Default")
      (node (ref "U1") (pin "B1") (pinfunction "PC15-OSC32_OUT_B1") (pintype "bidirectional"))
    )
    (net (code "84") (name "unconnected-(U1A-PD0-PadD8)") (class "Default")
      (node (ref "U1") (pin "D8") (pinfunction "PD0_D8") (pintype "bidirectional"))
    )
    (net (code "85") (name "unconnected-(U1A-PD1-PadE8)") (class "Default")
      (node (ref "U1") (pin "E8") (pinfunction "PD1_E8") (pintype "bidirectional"))
    )
    (net (code "86") (name "unconnected-(U1A-PD2-PadB7)") (class "Default")
      (node (ref "U1") (pin "B7") (pinfunction "PD2_B7") (pintype "bidirectional"))
    )
    (net (code "87") (name "unconnected-(U1A-PD3-PadC7)") (class "Default")
      (node (ref "U1") (pin "C7") (pinfunction "PD3_C7") (pintype "bidirectional"))
    )
    (net (code "88") (name "unconnected-(U1A-PD4-PadD7)") (class "Default")
      (node (ref "U1") (pin "D7") (pinfunction "PD4_D7") (pintype "bidirectional"))
    )
    (net (code "89") (name "unconnected-(U1A-PD6-PadC6)") (class "Default")
      (node (ref "U1") (pin "C6") (pinfunction "PD6_C6") (pintype "bidirectional"))
    )
    (net (code "90") (name "unconnected-(U1A-PD7-PadD6)") (class "Default")
      (node (ref "U1") (pin "D6") (pinfunction "PD7_D6") (pintype "bidirectional"))
    )
    (net (code "91") (name "unconnected-(U1A-PD8-PadK9)") (class "Default")
      (node (ref "U1") (pin "K9") (pinfunction "PD8_K9") (pintype "bidirectional"))
    )
    (net (code "92") (name "unconnected-(U1A-PD9-PadJ9)") (class "Default")
      (node (ref "U1") (pin "J9") (pinfunction "PD9_J9") (pintype "bidirectional"))
    )
    (net (code "93") (name "unconnected-(U1A-PD10-PadH9)") (class "Default")
      (node (ref "U1") (pin "H9") (pinfunction "PD10_H9") (pintype "bidirectional"))
    )
    (net (code "94") (name "unconnected-(U1A-PD11-PadG9)") (class "Default")
      (node (ref "U1") (pin "G9") (pinfunction "PD11_G9") (pintype "bidirectional"))
    )
    (net (code "95") (name "unconnected-(U1A-PD12-PadK10)") (class "Default")
      (node (ref "U1") (pin "K10") (pinfunction "PD12_K10") (pintype "bidirectional"))
    )
    (net (code "96") (name "unconnected-(U1A-PD13-PadJ10)") (class "Default")
      (node (ref "U1") (pin "J10") (pinfunction "PD13_J10") (pintype "bidirectional"))
    )
    (net (code "97") (name "unconnected-(U1A-PD14-PadH8)") (class "Default")
      (node (ref "U1") (pin "H8") (pinfunction "PD14_H8") (pintype "bidirectional"))
    )
    (net (code "98") (name "unconnected-(U1A-PD15-PadG8)") (class "Default")
      (node (ref "U1") (pin "G8") (pinfunction "PD15_G8") (pintype "bidirectional"))
    )
    (net (code "99") (name "unconnected-(U1B-PDR_ON-PadF7)") (class "Default")
      (node (ref "U1") (pin "F7") (pinfunction "PDR_ON_F7") (pintype "bidirectional"))
    )
    (net (code "100") (name "unconnected-(U1B-PE0-PadD4)") (class "Default")
      (node (ref "U1") (pin "D4") (pinfunction "PE0_D4") (pintype "bidirectional"))
    )
    (net (code "101") (name "unconnected-(U1B-PE1-PadC4)") (class "Default")
      (node (ref "U1") (pin "C4") (pinfunction "PE1_C4") (pintype "bidirectional"))
    )
    (net (code "102") (name "unconnected-(U1B-PE2-PadA3)") (class "Default")
      (node (ref "U1") (pin "A3") (pinfunction "PE2_A3") (pintype "bidirectional"))
    )
    (net (code "103") (name "unconnected-(U1B-PE3-PadB3)") (class "Default")
      (node (ref "U1") (pin "B3") (pinfunction "PE3_B3") (pintype "bidirectional"))
    )
    (net (code "104") (name "unconnected-(U1B-PE4-PadC3)") (class "Default")
      (node (ref "U1") (pin "C3") (pinfunction "PE4_C3") (pintype "bidirectional"))
    )
    (net (code "105") (name "unconnected-(U1B-PE5-PadD3)") (class "Default")
      (node (ref "U1") (pin "D3") (pinfunction "PE5_D3") (pintype "bidirectional"))
    )
    (net (code "106") (name "unconnected-(U1B-PE6-PadE3)") (class "Default")
      (node (ref "U1") (pin "E3") (pinfunction "PE6_E3") (pintype "bidirectional"))
    )
    (net (code "107") (name "unconnected-(U1B-PE7-PadH5)") (class "Default")
      (node (ref "U1") (pin "H5") (pinfunction "PE7_H5") (pintype "bidirectional"))
    )
    (net (code "108") (name "unconnected-(U1B-PE8-PadJ5)") (class "Default")
      (node (ref "U1") (pin "J5") (pinfunction "PE8_J5") (pintype "bidirectional"))
    )
    (net (code "109") (name "unconnected-(U1B-PE9-PadK5)") (class "Default")
      (node (ref "U1") (pin "K5") (pinfunction "PE9_K5") (pintype "bidirectional"))
    )
    (net (code "110") (name "unconnected-(U1B-PE10-PadG6)") (class "Default")
      (node (ref "U1") (pin "G6") (pinfunction "PE10_G6") (pintype "bidirectional"))
    )
    (net (code "111") (name "unconnected-(U1B-PE11-PadH6)") (class "Default")
      (node (ref "U1") (pin "H6") (pinfunction "PE11_H6") (pintype "bidirectional"))
    )
    (net (code "112") (name "unconnected-(U1B-PE12-PadJ6)") (class "Default")
      (node (ref "U1") (pin "J6") (pinfunction "PE12_J6") (pintype "bidirectional"))
    )
    (net (code "113") (name "unconnected-(U1B-PE13-PadK6)") (class "Default")
      (node (ref "U1") (pin "K6") (pinfunction "PE13_K6") (pintype "bidirectional"))
    )
    (net (code "114") (name "unconnected-(U1B-PE14-PadG7)") (class "Default")
      (node (ref "U1") (pin "G7") (pinfunction "PE14_G7") (pintype "bidirectional"))
    )
    (net (code "115") (name "unconnected-(U1B-PE15-PadH7)") (class "Default")
      (node (ref "U1") (pin "H7") (pinfunction "PE15_H7") (pintype "bidirectional"))
    )
    (net (code "116") (name "unconnected-(U2-EP-Pad9)") (class "Default")
      (node (ref "U2") (pin "9") (pinfunction "EP_9") (pintype "passive"))
    )
    (net (code "117") (name "unconnected-(U3-RESV-Pad2)") (class "Default")
      (node (ref "U3") (pin "2") (pinfunction "RESV_2") (pintype "passive"))
    )
    (net (code "118") (name "unconnected-(U3-RESV-Pad3)") (class "Default")
      (node (ref "U3") (pin "3") (pinfunction "RESV_3") (pintype "passive"))
    )
    (net (code "119") (name "unconnected-(U3-RESV-Pad10)") (class "Default")
      (node (ref "U3") (pin "10") (pinfunction "RESV_10") (pintype "passive"))
    )
    (net (code "120") (name "unconnected-(U5-EP-Pad9)") (class "Default")
      (node (ref "U5") (pin "9") (pinfunction "EP_9") (pintype "passive"))
    )
  )
)
